# SCH_Teensy-PWM-Machine_2025-12-06_1.net
KiCad netlist of a schematic drawn in EasyEDA
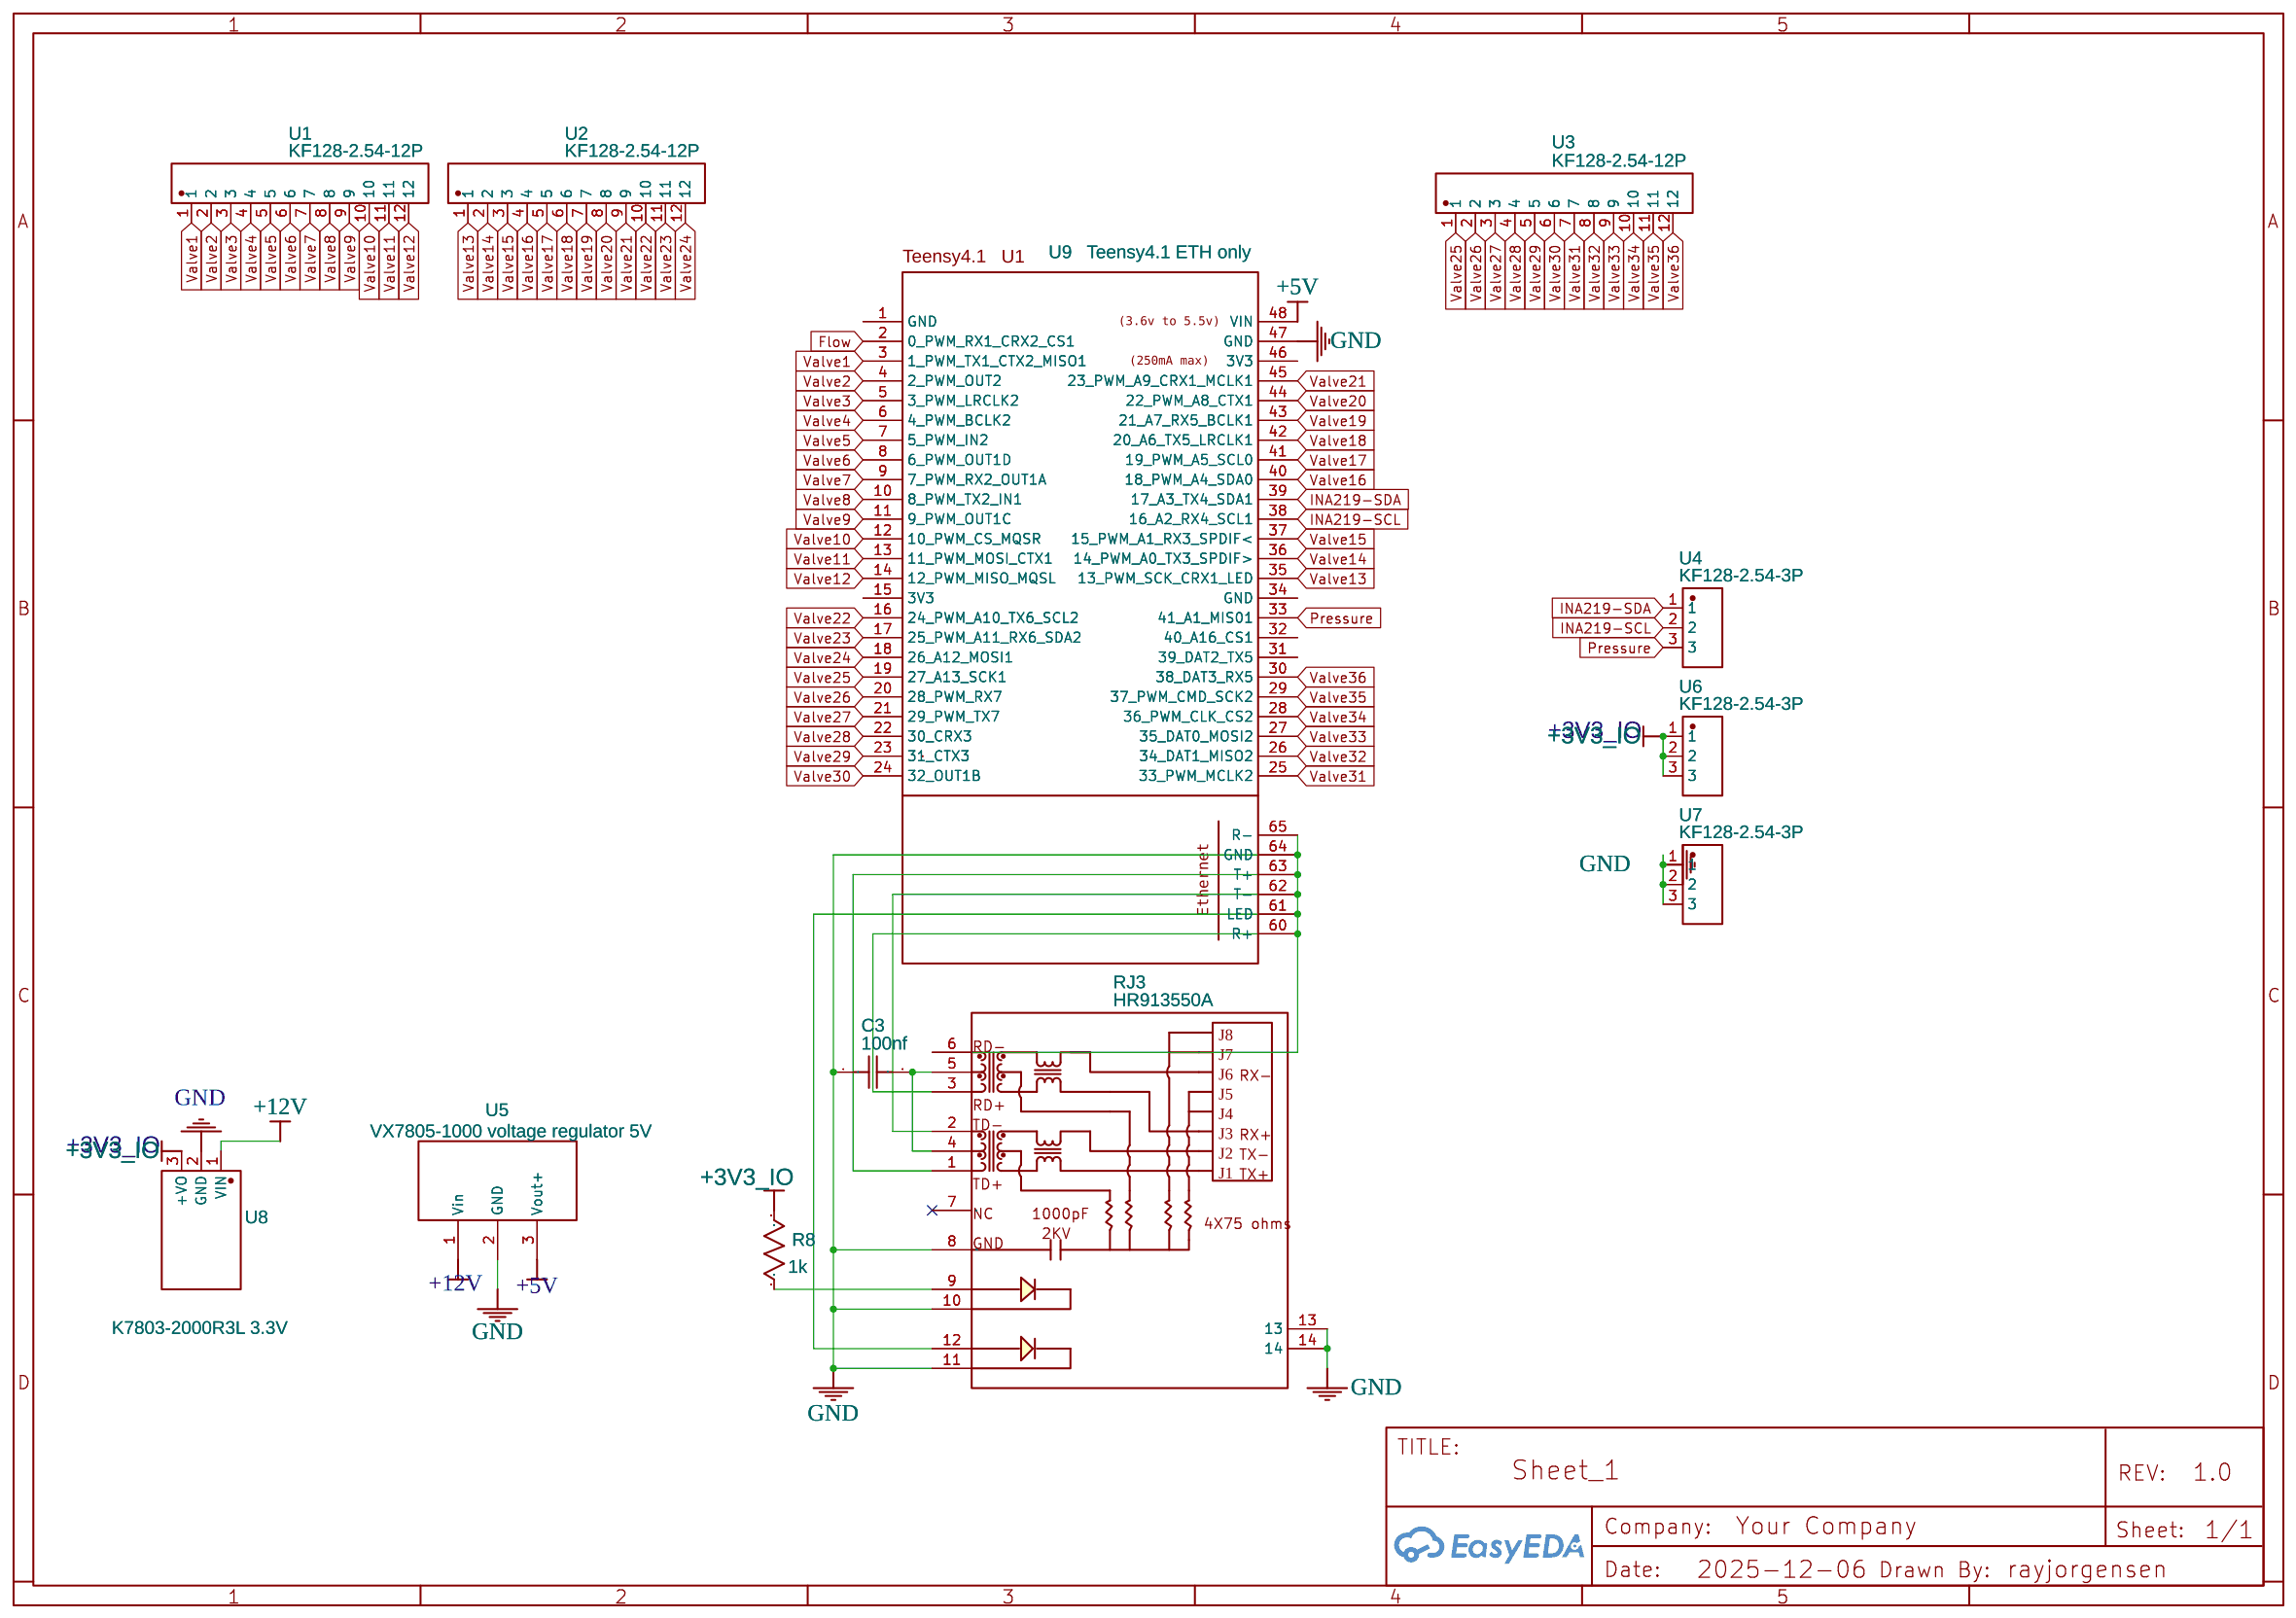
[diagram p0: schematic sheet]

(export (version "E")
  (design (tool "Eeschema 10.0.6"))
  (components
    (comp (ref "C3") (value "100nf") (libsource (lib "") (part "C_RAD-0.1_US")))
    (comp (ref "R8") (value "1k") (libsource (lib "") (part "R_AXIAL-0.4_US")))
    (comp (ref "RJ3")
      (value "HR913550A")
      (fields (field (name "Manufacturer") "HANRUN"))
      (libsource (lib "") (part "HR913550A"))
    )
    (comp (ref "U1")
      (value "KF128-2.54-12P")
      (fields (field (name "Manufacturer") "KEFA(科发)"))
      (libsource (lib "") (part "KF128-2.54-12P"))
    )
    (comp (ref "U2")
      (value "KF128-2.54-12P")
      (fields (field (name "Manufacturer") "KEFA(科发)"))
      (libsource (lib "") (part "KF128-2.54-12P"))
    )
    (comp (ref "U3")
      (value "KF128-2.54-12P")
      (fields (field (name "Manufacturer") "KEFA(科发)"))
      (libsource (lib "") (part "KF128-2.54-12P"))
    )
    (comp (ref "U4")
      (value "KF128-2.54-3P")
      (fields (field (name "Manufacturer") "KEFA(科发)"))
      (libsource (lib "") (part "KF128-2.54-3P"))
    )
    (comp (ref "U5")
      (value "VX7805-1000 voltage regulator 5V")
      (fields (field (name "Manufacturer Part") "VX7805-1000") (field (name "Manufacturer") "CUI"))
      (libsource (lib "") (part "VX7805-1000 voltage regulator"))
    )
    (comp (ref "U6")
      (value "KF128-2.54-3P")
      (fields (field (name "Manufacturer") "KEFA(科发)"))
      (libsource (lib "") (part "KF128-2.54-3P"))
    )
    (comp (ref "U7")
      (value "KF128-2.54-3P")
      (fields (field (name "Manufacturer") "KEFA(科发)"))
      (libsource (lib "") (part "KF128-2.54-3P"))
    )
    (comp (ref "U8")
      (value "K7803-2000R3L 3.3V")
      (fields
        (field (name "Manufacturer Part") "K7803-2000")
        (field (name "Manufacturer") "MORNSUN Guangzhou S& T")
      )
      (libsource (lib "") (part "K7803-2000R3L"))
    )
    (comp (ref "U9")
      (value "Teensy4.1 ETH only")
      (fields (field (name "Manufacturer Part") "Teensy4.1") (field (name "Manufacturer") "PJRC"))
      (libsource (lib "") (part "Teensy4.1 ETH only"))
    )
  )
  (nets
    (net (code "1") (name "+3V3_IO") (class "Default")
      (node (ref "R8") (pin "2") (pinfunction "2_2") (pintype "unspecified"))
      (node (ref "U6") (pin "1") (pinfunction "1_1") (pintype "unspecified"))
      (node (ref "U6") (pin "2") (pinfunction "2_2") (pintype "unspecified"))
      (node (ref "U6") (pin "3") (pinfunction "3_3") (pintype "unspecified"))
      (node (ref "U8") (pin "3") (pinfunction "+VO_3") (pintype "unspecified"))
    )
    (net (code "2") (name "+5V") (class "Default")
      (node (ref "U5") (pin "3") (pinfunction "Vout+_3") (pintype "unspecified"))
      (node (ref "U9") (pin "48") (pinfunction "VIN_48") (pintype "bidirectional"))
    )
    (net (code "3") (name "+12V") (class "Default")
      (node (ref "U5") (pin "1") (pinfunction "Vin_1") (pintype "unspecified"))
      (node (ref "U8") (pin "1") (pinfunction "VIN_1") (pintype "unspecified"))
    )
    (net (code "4") (name "Flow") (class "Default")
      (node (ref "U9") (pin "2") (pinfunction "0_PWM_RX1_CRX2_CS1_2") (pintype "bidirectional"))
    )
    (net (code "5") (name "GND") (class "Default")
      (node (ref "C3") (pin "1") (pinfunction "1_1") (pintype "unspecified"))
      (node (ref "RJ3") (pin "1") (pintype "unspecified"))
      (node (ref "RJ3") (pin "10") (pintype "unspecified"))
      (node (ref "RJ3") (pin "11") (pintype "unspecified"))
      (node (ref "RJ3") (pin "12") (pintype "unspecified"))
      (node (ref "RJ3") (pin "13") (pinfunction "13_13") (pintype "unspecified"))
      (node (ref "RJ3") (pin "14") (pinfunction "14_14") (pintype "unspecified"))
      (node (ref "RJ3") (pin "2") (pintype "unspecified"))
      (node (ref "RJ3") (pin "3") (pintype "unspecified"))
      (node (ref "RJ3") (pin "6") (pintype "unspecified"))
      (node (ref "RJ3") (pin "8") (pinfunction "GND_8") (pintype "unspecified"))
      (node (ref "U5") (pin "2") (pinfunction "GND_2") (pintype "unspecified"))
      (node (ref "U7") (pin "1") (pinfunction "1_1") (pintype "unspecified"))
      (node (ref "U7") (pin "2") (pinfunction "2_2") (pintype "unspecified"))
      (node (ref "U7") (pin "3") (pinfunction "3_3") (pintype "unspecified"))
      (node (ref "U8") (pin "2") (pinfunction "GND_2") (pintype "unspecified"))
      (node (ref "U9") (pin "47") (pinfunction "GND_47") (pintype "bidirectional"))
      (node (ref "U9") (pin "60") (pinfunction "R+_60") (pintype "bidirectional"))
      (node (ref "U9") (pin "61") (pinfunction "LED_61") (pintype "bidirectional"))
      (node (ref "U9") (pin "62") (pinfunction "T-_62") (pintype "bidirectional"))
      (node (ref "U9") (pin "63") (pinfunction "T+_63") (pintype "bidirectional"))
      (node (ref "U9") (pin "64") (pinfunction "GND_64") (pintype "bidirectional"))
      (node (ref "U9") (pin "65") (pinfunction "R-_65") (pintype "bidirectional"))
    )
    (net (code "6") (name "INA219-SCL") (class "Default")
      (node (ref "U4") (pin "2") (pinfunction "2_2") (pintype "unspecified"))
      (node (ref "U9") (pin "38") (pinfunction "16_A2_RX4_SCL1_38") (pintype "bidirectional"))
    )
    (net (code "7") (name "INA219-SDA") (class "Default")
      (node (ref "U4") (pin "1") (pinfunction "1_1") (pintype "unspecified"))
      (node (ref "U9") (pin "39") (pinfunction "17_A3_TX4_SDA1_39") (pintype "bidirectional"))
    )
    (net (code "8") (name "Net-(C3-Pad2)") (class "Default")
      (node (ref "C3") (pin "2") (pinfunction "2_2") (pintype "unspecified"))
      (node (ref "RJ3") (pin "4") (pintype "unspecified"))
      (node (ref "RJ3") (pin "5") (pintype "unspecified"))
    )
    (net (code "9") (name "Net-(R8-Pad1)") (class "Default")
      (node (ref "R8") (pin "1") (pinfunction "1_1") (pintype "unspecified"))
      (node (ref "RJ3") (pin "9") (pintype "unspecified"))
    )
    (net (code "10") (name "Pressure") (class "Default")
      (node (ref "U4") (pin "3") (pinfunction "3_3") (pintype "unspecified"))
      (node (ref "U9") (pin "33") (pinfunction "41_A1_MIS01_33") (pintype "bidirectional"))
    )
    (net (code "11") (name "Valve1") (class "Default")
      (node (ref "U1") (pin "1") (pinfunction "1_1") (pintype "unspecified"))
      (node (ref "U9") (pin "3") (pinfunction "1_PWM_TX1_CTX2_MISO1_3") (pintype "bidirectional"))
    )
    (net (code "12") (name "Valve2") (class "Default")
      (node (ref "U1") (pin "2") (pinfunction "2_2") (pintype "unspecified"))
      (node (ref "U9") (pin "4") (pinfunction "2_PWM_OUT2_4") (pintype "bidirectional"))
    )
    (net (code "13") (name "Valve3") (class "Default")
      (node (ref "U1") (pin "3") (pinfunction "3_3") (pintype "unspecified"))
      (node (ref "U9") (pin "5") (pinfunction "3_PWM_LRCLK2_5") (pintype "bidirectional"))
    )
    (net (code "14") (name "Valve4") (class "Default")
      (node (ref "U1") (pin "4") (pinfunction "4_4") (pintype "unspecified"))
      (node (ref "U9") (pin "6") (pinfunction "4_PWM_BCLK2_6") (pintype "bidirectional"))
    )
    (net (code "15") (name "Valve5") (class "Default")
      (node (ref "U1") (pin "5") (pinfunction "5_5") (pintype "unspecified"))
      (node (ref "U9") (pin "7") (pinfunction "5_PWM_IN2_7") (pintype "bidirectional"))
    )
    (net (code "16") (name "Valve6") (class "Default")
      (node (ref "U1") (pin "6") (pinfunction "6_6") (pintype "unspecified"))
      (node (ref "U9") (pin "8") (pinfunction "6_PWM_OUT1D_8") (pintype "bidirectional"))
    )
    (net (code "17") (name "Valve7") (class "Default")
      (node (ref "U1") (pin "7") (pinfunction "7_7") (pintype "unspecified"))
      (node (ref "U9") (pin "9") (pinfunction "7_PWM_RX2_OUT1A_9") (pintype "bidirectional"))
    )
    (net (code "18") (name "Valve8") (class "Default")
      (node (ref "U1") (pin "8") (pinfunction "8_8") (pintype "unspecified"))
      (node (ref "U9") (pin "10") (pinfunction "8_PWM_TX2_IN1_10") (pintype "bidirectional"))
    )
    (net (code "19") (name "Valve9") (class "Default")
      (node (ref "U1") (pin "9") (pinfunction "9_9") (pintype "unspecified"))
      (node (ref "U9") (pin "11") (pinfunction "9_PWM_OUT1C_11") (pintype "bidirectional"))
    )
    (net (code "20") (name "Valve10") (class "Default")
      (node (ref "U1") (pin "10") (pinfunction "10_10") (pintype "unspecified"))
      (node (ref "U9") (pin "12") (pinfunction "10_PWM_CS_MQSR_12") (pintype "bidirectional"))
    )
    (net (code "21") (name "Valve11") (class "Default")
      (node (ref "U1") (pin "11") (pinfunction "11_11") (pintype "unspecified"))
      (node (ref "U9") (pin "13") (pinfunction "11_PWM_MOSI_CTX1_13") (pintype "bidirectional"))
    )
    (net (code "22") (name "Valve12") (class "Default")
      (node (ref "U1") (pin "12") (pinfunction "12_12") (pintype "unspecified"))
      (node (ref "U9") (pin "14") (pinfunction "12_PWM_MISO_MQSL_14") (pintype "bidirectional"))
    )
    (net (code "23") (name "Valve13") (class "Default")
      (node (ref "U2") (pin "1") (pinfunction "1_1") (pintype "unspecified"))
      (node (ref "U9") (pin "35") (pinfunction "13_PWM_SCK_CRX1_LED_35") (pintype "bidirectional"))
    )
    (net (code "24") (name "Valve14") (class "Default")
      (node (ref "U2") (pin "2") (pinfunction "2_2") (pintype "unspecified"))
      (node (ref "U9") (pin "36") (pinfunction "14_PWM_A0_TX3_SPDIF>_36") (pintype "bidirectional"))
    )
    (net (code "25") (name "Valve15") (class "Default")
      (node (ref "U2") (pin "3") (pinfunction "3_3") (pintype "unspecified"))
      (node (ref "U9") (pin "37") (pinfunction "15_PWM_A1_RX3_SPDIF<_37") (pintype "bidirectional"))
    )
    (net (code "26") (name "Valve16") (class "Default")
      (node (ref "U2") (pin "4") (pinfunction "4_4") (pintype "unspecified"))
      (node (ref "U9") (pin "40") (pinfunction "18_PWM_A4_SDA0_40") (pintype "bidirectional"))
    )
    (net (code "27") (name "Valve17") (class "Default")
      (node (ref "U2") (pin "5") (pinfunction "5_5") (pintype "unspecified"))
      (node (ref "U9") (pin "41") (pinfunction "19_PWM_A5_SCL0_41") (pintype "bidirectional"))
    )
    (net (code "28") (name "Valve18") (class "Default")
      (node (ref "U2") (pin "6") (pinfunction "6_6") (pintype "unspecified"))
      (node (ref "U9") (pin "42") (pinfunction "20_A6_TX5_LRCLK1_42") (pintype "bidirectional"))
    )
    (net (code "29") (name "Valve19") (class "Default")
      (node (ref "U2") (pin "7") (pinfunction "7_7") (pintype "unspecified"))
      (node (ref "U9") (pin "43") (pinfunction "21_A7_RX5_BCLK1_43") (pintype "bidirectional"))
    )
    (net (code "30") (name "Valve20") (class "Default")
      (node (ref "U2") (pin "8") (pinfunction "8_8") (pintype "unspecified"))
      (node (ref "U9") (pin "44") (pinfunction "22_PWM_A8_CTX1_44") (pintype "bidirectional"))
    )
    (net (code "31") (name "Valve21") (class "Default")
      (node (ref "U2") (pin "9") (pinfunction "9_9") (pintype "unspecified"))
      (node (ref "U9") (pin "45") (pinfunction "23_PWM_A9_CRX1_MCLK1_45") (pintype "bidirectional"))
    )
    (net (code "32") (name "Valve22") (class "Default")
      (node (ref "U2") (pin "10") (pinfunction "10_10") (pintype "unspecified"))
      (node (ref "U9") (pin "16") (pinfunction "24_PWM_A10_TX6_SCL2_16") (pintype "bidirectional"))
    )
    (net (code "33") (name "Valve23") (class "Default")
      (node (ref "U2") (pin "11") (pinfunction "11_11") (pintype "unspecified"))
      (node (ref "U9") (pin "17") (pinfunction "25_PWM_A11_RX6_SDA2_17") (pintype "bidirectional"))
    )
    (net (code "34") (name "Valve24") (class "Default")
      (node (ref "U2") (pin "12") (pinfunction "12_12") (pintype "unspecified"))
      (node (ref "U9") (pin "18") (pinfunction "26_A12_MOSI1_18") (pintype "bidirectional"))
    )
    (net (code "35") (name "Valve25") (class "Default")
      (node (ref "U3") (pin "1") (pinfunction "1_1") (pintype "unspecified"))
      (node (ref "U9") (pin "19") (pinfunction "27_A13_SCK1_19") (pintype "bidirectional"))
    )
    (net (code "36") (name "Valve26") (class "Default")
      (node (ref "U3") (pin "2") (pinfunction "2_2") (pintype "unspecified"))
      (node (ref "U9") (pin "20") (pinfunction "28_PWM_RX7_20") (pintype "bidirectional"))
    )
    (net (code "37") (name "Valve27") (class "Default")
      (node (ref "U3") (pin "3") (pinfunction "3_3") (pintype "unspecified"))
      (node (ref "U9") (pin "21") (pinfunction "29_PWM_TX7_21") (pintype "bidirectional"))
    )
    (net (code "38") (name "Valve28") (class "Default")
      (node (ref "U3") (pin "4") (pinfunction "4_4") (pintype "unspecified"))
      (node (ref "U9") (pin "22") (pinfunction "30_CRX3_22") (pintype "bidirectional"))
    )
    (net (code "39") (name "Valve29") (class "Default")
      (node (ref "U3") (pin "5") (pinfunction "5_5") (pintype "unspecified"))
      (node (ref "U9") (pin "23") (pinfunction "31_CTX3_23") (pintype "bidirectional"))
    )
    (net (code "40") (name "Valve30") (class "Default")
      (node (ref "U3") (pin "6") (pinfunction "6_6") (pintype "unspecified"))
      (node (ref "U9") (pin "24") (pinfunction "32_OUT1B_24") (pintype "bidirectional"))
    )
    (net (code "41") (name "Valve31") (class "Default")
      (node (ref "U3") (pin "7") (pinfunction "7_7") (pintype "unspecified"))
      (node (ref "U9") (pin "25") (pinfunction "33_PWM_MCLK2_25") (pintype "bidirectional"))
    )
    (net (code "42") (name "Valve32") (class "Default")
      (node (ref "U3") (pin "8") (pinfunction "8_8") (pintype "unspecified"))
      (node (ref "U9") (pin "26") (pinfunction "34_DAT1_MISO2_26") (pintype "bidirectional"))
    )
    (net (code "43") (name "Valve33") (class "Default")
      (node (ref "U3") (pin "9") (pinfunction "9_9") (pintype "unspecified"))
      (node (ref "U9") (pin "27") (pinfunction "35_DAT0_MOSI2_27") (pintype "bidirectional"))
    )
    (net (code "44") (name "Valve34") (class "Default")
      (node (ref "U3") (pin "10") (pinfunction "10_10") (pintype "unspecified"))
      (node (ref "U9") (pin "28") (pinfunction "36_PWM_CLK_CS2_28") (pintype "bidirectional"))
    )
    (net (code "45") (name "Valve35") (class "Default")
      (node (ref "U3") (pin "11") (pinfunction "11_11") (pintype "unspecified"))
      (node (ref "U9") (pin "29") (pinfunction "37_PWM_CMD_SCK2_29") (pintype "bidirectional"))
    )
    (net (code "46") (name "Valve36") (class "Default")
      (node (ref "U3") (pin "12") (pinfunction "12_12") (pintype "unspecified"))
      (node (ref "U9") (pin "30") (pinfunction "38_DAT3_RX5_30") (pintype "bidirectional"))
    )
    (net (code "47") (name "unconnected-(RJ3-NC-Pad7)") (class "Default")
      (node (ref "RJ3") (pin "7") (pinfunction "NC_7") (pintype "unspecified+no_connect"))
    )
    (net (code "48") (name "unconnected-(U9-3V3-Pad15)") (class "Default")
      (node (ref "U9") (pin "15") (pinfunction "3V3_15") (pintype "bidirectional"))
    )
    (net (code "49") (name "unconnected-(U9-3V3-Pad46)") (class "Default")
      (node (ref "U9") (pin "46") (pinfunction "3V3_46") (pintype "bidirectional"))
    )
    (net (code "50") (name "unconnected-(U9-39_DAT2_TX5-Pad31)") (class "Default")
      (node (ref "U9") (pin "31") (pinfunction "39_DAT2_TX5_31") (pintype "bidirectional"))
    )
    (net (code "51") (name "unconnected-(U9-40_A16_CS1-Pad32)") (class "Default")
      (node (ref "U9") (pin "32") (pinfunction "40_A16_CS1_32") (pintype "bidirectional"))
    )
    (net (code "52") (name "unconnected-(U9-GND-Pad1)") (class "Default")
      (node (ref "U9") (pin "1") (pinfunction "GND_1") (pintype "bidirectional"))
    )
    (net (code "53") (name "unconnected-(U9-GND-Pad34)") (class "Default")
      (node (ref "U9") (pin "34") (pinfunction "GND_34") (pintype "bidirectional"))
    )
  )
)
